# Power.net
KiCad netlist of a schematic drawn in Altium Designer
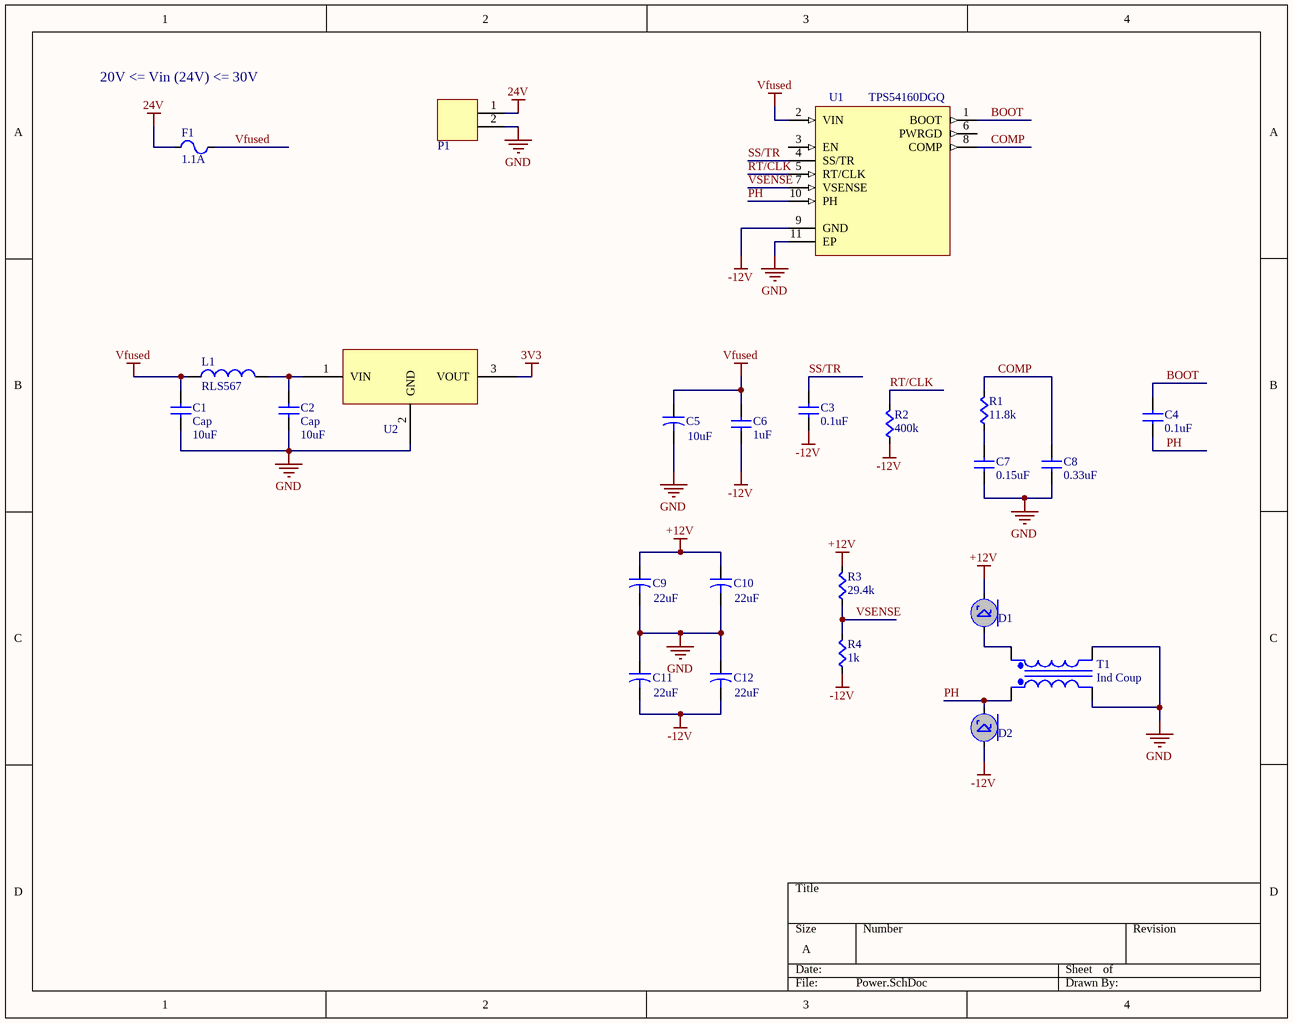
[diagram p0: Power.SchDoc]

(export (version "E")
  (design (tool "Eeschema 10.0.6"))
  (components
    (comp (ref "C1")
      (value "Cap")
      (footprint "CAP1210")
      (description "CAP CER 10UF 50V 20% X5R 1210")
      (fields (field (name "ALTIUM_VALUE") "10uF"))
      (libsource (lib "SubjuGator8") (part "CAP1210"))
    )
    (comp (ref "C2")
      (value "Cap")
      (footprint "CAP1210")
      (description "CAP CER 10UF 50V 20% X5R 1210")
      (fields (field (name "ALTIUM_VALUE") "10uF"))
      (libsource (lib "SubjuGator8") (part "CAP1210"))
    )
    (comp (ref "C3")
      (value "0.1uF")
      (footprint "CAPC0603")
      (fields (field (name "Comment") "EEHZA1H101P"))
      (libsource (lib "SubjuGator8") (part "Cap"))
    )
    (comp (ref "C4")
      (value "0.1uF")
      (footprint "CAPC0603")
      (fields (field (name "Comment") "Cap"))
      (libsource (lib "SubjuGator8") (part "Cap"))
    )
    (comp (ref "C5")
      (value "10uF")
      (footprint "CAPR5-4X5")
      (description "Capacitor")
      (fields (field (name "Comment") "Cap2") (field (name "PUBLISHER") "Altium Limited"))
      (libsource (lib "Miscellaneous Devices") (part "Cap2"))
    )
    (comp (ref "C6")
      (value "1uF")
      (footprint "CAPC0603")
      (fields (field (name "Comment") "Cap"))
      (libsource (lib "SubjuGator8") (part "Cap"))
    )
    (comp (ref "C7")
      (value "0.15uF")
      (footprint "CAPC0603")
      (fields (field (name "Comment") "Cap"))
      (libsource (lib "SubjuGator8") (part "Cap"))
    )
    (comp (ref "C8")
      (value "0.33uF")
      (footprint "CAPC0603")
      (fields (field (name "Comment") "Cap"))
      (libsource (lib "SubjuGator8") (part "Cap"))
    )
    (comp (ref "C9")
      (value "22uF")
      (footprint "CAPR5-4X5")
      (description "Capacitor")
      (fields (field (name "Comment") "Cap2") (field (name "PUBLISHER") "Altium Limited"))
      (libsource (lib "Miscellaneous Devices") (part "Cap2"))
    )
    (comp (ref "C10")
      (value "22uF")
      (footprint "CAPR5-4X5")
      (description "Capacitor")
      (fields (field (name "Comment") "Cap2") (field (name "PUBLISHER") "Altium Limited"))
      (libsource (lib "Miscellaneous Devices") (part "Cap2"))
    )
    (comp (ref "C11")
      (value "22uF")
      (footprint "CAPR5-4X5")
      (description "Capacitor")
      (fields (field (name "Comment") "Cap2") (field (name "PUBLISHER") "Altium Limited"))
      (libsource (lib "Miscellaneous Devices") (part "Cap2"))
    )
    (comp (ref "C12")
      (value "22uF")
      (footprint "CAPR5-4X5")
      (description "Capacitor")
      (fields (field (name "Comment") "Cap2") (field (name "PUBLISHER") "Altium Limited"))
      (libsource (lib "Miscellaneous Devices") (part "Cap2"))
    )
    (comp (ref "D1")
      (value "Schottky")
      (footprint "DSS16UTR")
      (description "Schottky Diode Template")
      (libsource (lib "SubjuGator8") (part "Schottky"))
    )
    (comp (ref "D2")
      (value "Schottky")
      (footprint "DSS16UTR")
      (description "Schottky Diode Template")
      (libsource (lib "SubjuGator8") (part "Schottky"))
    )
    (comp (ref "F1")
      (value "1.1A")
      (footprint "PTC7451X11N")
      (fields (field (name "Comment") "PTC Fuse"))
      (libsource (lib "SubjuGator8") (part "PTC_Fuse"))
    )
    (comp (ref "L1")
      (value "Inductor")
      (footprint "RLS567")
      (fields (field (name "INDUCTANCE") "RLS567"))
      (libsource (lib "SubjuGator8") (part "Inductor"))
    )
    (comp (ref "P1")
      (value "2-pin Vert Sherlock")
      (footprint "MOLEX-HDR-1X2-SHERLOCK-VERT")
      (libsource (lib "SubjuGator8") (part "MOLEX-HDR-1x2-SHERLOCK_VERT"))
    )
    (comp (ref "R1")
      (value "11.8k")
      (footprint "RES1206")
      (fields (field (name "Comment") "Res"))
      (libsource (lib "SubjuGator8") (part "Res"))
    )
    (comp (ref "R2")
      (value "400k")
      (footprint "RES1206")
      (fields (field (name "Comment") "Res"))
      (libsource (lib "SubjuGator8") (part "Res"))
    )
    (comp (ref "R3")
      (value "29.4k")
      (footprint "RES1206")
      (fields (field (name "Comment") "Res"))
      (libsource (lib "SubjuGator8") (part "Res"))
    )
    (comp (ref "R4")
      (value "1k")
      (footprint "RES0603")
      (fields (field (name "Comment") "Res"))
      (libsource (lib "SubjuGator8") (part "Res"))
    )
    (comp (ref "T1")
      (value "Ind Coup")
      (footprint "SOP4")
      (description "Transformer (Coupled Inductor Model)")
      (fields (field (name "PUBLISHER") "Altium Limited"))
      (libsource (lib "Miscellaneous Devices") (part "Trans Cupl"))
    )
    (comp (ref "U1")
      (value "TPS54160DGQ")
      (footprint "SOIC-11")
      (fields (field (name "MF") "Texas Instruments"))
      (libsource (lib "SubjuGator8") (part "TPS54160DGQ"))
    )
    (comp (ref "U2")
      (value "R-78C3.3-1.0")
      (footprint "R-78C3.3-1.0")
      (description "CONV DC/DC 1A 3.3V OUT SIP VERT")
      (libsource (lib "SubjuGator8") (part "R-78C3.3-1.0"))
    )
  )
  (nets
    (net (code "1") (name "+12V") (class "Default")
      (node (ref "C10") (pin "1") (pinfunction "1_1") (pintype "passive"))
      (node (ref "C9") (pin "1") (pinfunction "1_1") (pintype "passive"))
      (node (ref "D1") (pin "C") (pinfunction "C_C") (pintype "passive"))
      (node (ref "R3") (pin "1") (pinfunction "A_1") (pintype "passive"))
    )
    (net (code "2") (name "-12V") (class "Default")
      (node (ref "C11") (pin "2") (pinfunction "2_2") (pintype "passive"))
      (node (ref "C12") (pin "2") (pinfunction "2_2") (pintype "passive"))
      (node (ref "C3") (pin "2") (pinfunction "B_2") (pintype "passive"))
      (node (ref "C6") (pin "2") (pinfunction "B_2") (pintype "passive"))
      (node (ref "D2") (pin "A") (pinfunction "A_A") (pintype "passive"))
      (node (ref "R2") (pin "2") (pinfunction "B_2") (pintype "passive"))
      (node (ref "R4") (pin "2") (pinfunction "B_2") (pintype "passive"))
      (node (ref "U1") (pin "9") (pinfunction "GND_9") (pintype "passive"))
    )
    (net (code "3") (name "/BOOT") (class "Default")
      (node (ref "C4") (pin "1") (pinfunction "A_1") (pintype "passive"))
      (node (ref "U1") (pin "1") (pinfunction "BOOT_1") (pintype "output"))
    )
    (net (code "4") (name "/COMP") (class "Default")
      (node (ref "C8") (pin "1") (pinfunction "A_1") (pintype "passive"))
      (node (ref "R1") (pin "1") (pinfunction "A_1") (pintype "passive"))
      (node (ref "U1") (pin "8") (pinfunction "COMP_8") (pintype "output"))
    )
    (net (code "5") (name "/PH") (class "Default")
      (node (ref "C4") (pin "2") (pinfunction "B_2") (pintype "passive"))
      (node (ref "D2") (pin "C") (pinfunction "C_C") (pintype "passive"))
      (node (ref "T1") (pin "4") (pinfunction "Pri+_4") (pintype "passive"))
      (node (ref "U1") (pin "10") (pinfunction "PH_10") (pintype "input"))
    )
    (net (code "6") (name "/RT{slash}CLK") (class "Default")
      (node (ref "R2") (pin "1") (pinfunction "A_1") (pintype "passive"))
      (node (ref "U1") (pin "5") (pinfunction "RT/CLK_5") (pintype "input"))
    )
    (net (code "7") (name "/SS{slash}TR") (class "Default")
      (node (ref "C3") (pin "1") (pinfunction "A_1") (pintype "passive"))
      (node (ref "U1") (pin "4") (pinfunction "SS/TR_4") (pintype "power_in"))
    )
    (net (code "8") (name "/VSENSE") (class "Default")
      (node (ref "R3") (pin "2") (pinfunction "B_2") (pintype "passive"))
      (node (ref "R4") (pin "1") (pinfunction "A_1") (pintype "passive"))
      (node (ref "U1") (pin "7") (pinfunction "VSENSE_7") (pintype "input"))
    )
    (net (code "9") (name "3V3") (class "Default")
      (node (ref "U2") (pin "3") (pinfunction "VOUT_3") (pintype "passive"))
    )
    (net (code "10") (name "24V") (class "Default")
      (node (ref "F1") (pin "1") (pinfunction "A_1") (pintype "passive"))
      (node (ref "P1") (pin "1") (pinfunction "1_1") (pintype "passive"))
    )
    (net (code "11") (name "GND") (class "Default")
      (node (ref "C1") (pin "2") (pinfunction "B_2") (pintype "passive"))
      (node (ref "C10") (pin "2") (pinfunction "2_2") (pintype "passive"))
      (node (ref "C11") (pin "1") (pinfunction "1_1") (pintype "passive"))
      (node (ref "C12") (pin "1") (pinfunction "1_1") (pintype "passive"))
      (node (ref "C2") (pin "2") (pinfunction "B_2") (pintype "passive"))
      (node (ref "C5") (pin "2") (pinfunction "2_2") (pintype "passive"))
      (node (ref "C7") (pin "2") (pinfunction "B_2") (pintype "passive"))
      (node (ref "C8") (pin "2") (pinfunction "B_2") (pintype "passive"))
      (node (ref "C9") (pin "2") (pinfunction "2_2") (pintype "passive"))
      (node (ref "P1") (pin "2") (pinfunction "2_2") (pintype "passive"))
      (node (ref "T1") (pin "1") (pinfunction "Pri-_1") (pintype "passive"))
      (node (ref "T1") (pin "2") (pinfunction "Sec-_2") (pintype "passive"))
      (node (ref "U1") (pin "11") (pinfunction "EP_11") (pintype "passive"))
      (node (ref "U2") (pin "2") (pinfunction "GND_2") (pintype "power_in"))
    )
    (net (code "12") (name "Net-(C2-A)") (class "Default")
      (node (ref "C2") (pin "1") (pinfunction "A_1") (pintype "passive"))
      (node (ref "L1") (pin "2") (pinfunction "B_2") (pintype "passive"))
      (node (ref "U2") (pin "1") (pinfunction "VIN_1") (pintype "passive"))
    )
    (net (code "13") (name "Net-(C7-A)") (class "Default")
      (node (ref "C7") (pin "1") (pinfunction "A_1") (pintype "passive"))
      (node (ref "R1") (pin "2") (pinfunction "B_2") (pintype "passive"))
    )
    (net (code "14") (name "Net-(T1-Sec+)") (class "Default")
      (node (ref "D1") (pin "A") (pinfunction "A_A") (pintype "passive"))
      (node (ref "T1") (pin "3") (pinfunction "Sec+_3") (pintype "passive"))
    )
    (net (code "15") (name "Vfused") (class "Default")
      (node (ref "C1") (pin "1") (pinfunction "A_1") (pintype "passive"))
      (node (ref "C5") (pin "1") (pinfunction "1_1") (pintype "passive"))
      (node (ref "C6") (pin "1") (pinfunction "A_1") (pintype "passive"))
      (node (ref "F1") (pin "2") (pinfunction "B_2") (pintype "passive"))
      (node (ref "L1") (pin "1") (pinfunction "A_1") (pintype "passive"))
      (node (ref "U1") (pin "2") (pinfunction "VIN_2") (pintype "input"))
    )
    (net (code "16") (name "unconnected-(U1-EN-Pad3)") (class "Default")
      (node (ref "U1") (pin "3") (pinfunction "EN_3") (pintype "input"))
    )
    (net (code "17") (name "unconnected-(U1-PWRGD-Pad6)") (class "Default")
      (node (ref "U1") (pin "6") (pinfunction "PWRGD_6") (pintype "output"))
    )
  )
)
